# wii.net
KiCad netlist of a schematic drawn in EAGLE
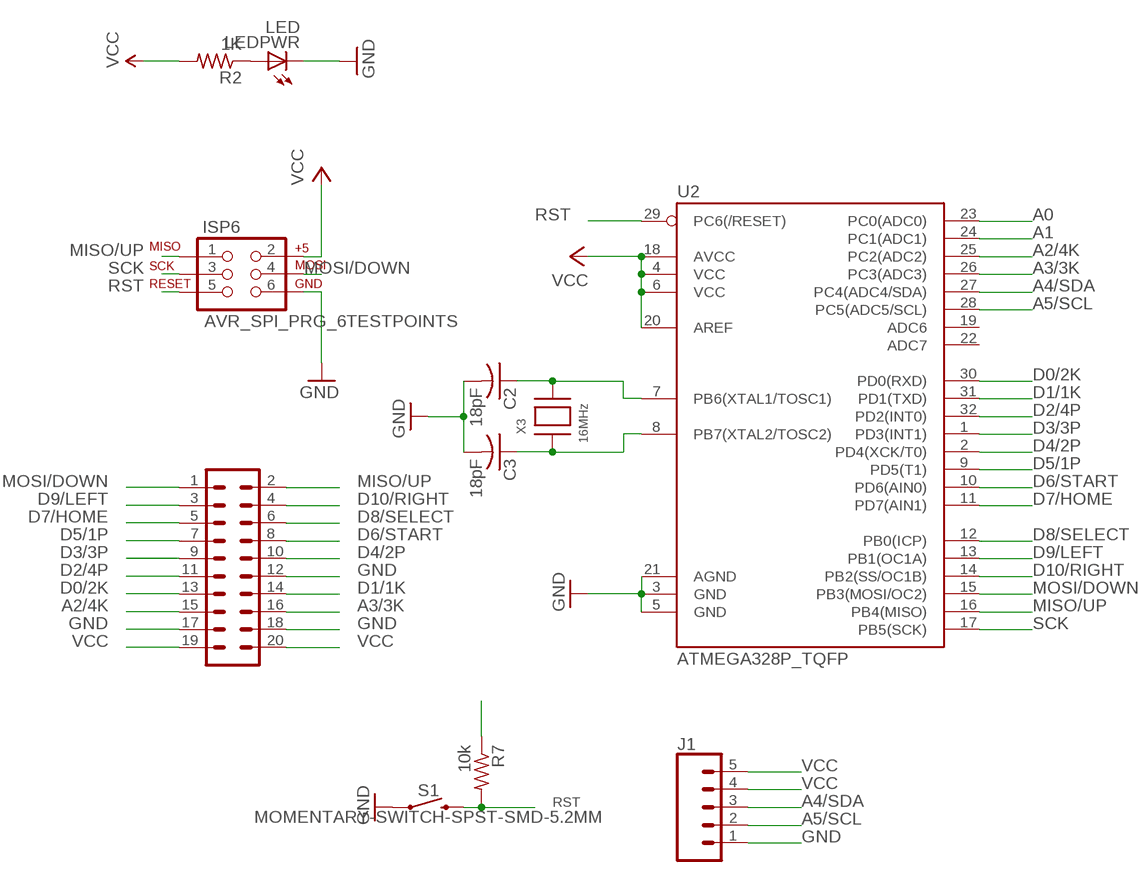
[diagram p0: schematic, sheet 1]

(export (version "E")
  (design (tool "Eeschema 10.0.6"))
  (components
    (comp (ref "C2")
      (value "18pF")
      (footprint "eagle-import:C0805")
      (libsource (lib "eagle-import") (part "C-USC0805"))
    )
    (comp (ref "C3")
      (value "18pF")
      (footprint "eagle-import:C0805")
      (libsource (lib "eagle-import") (part "C-USC0805"))
    )
    (comp (ref "ISP6")
      (value "AVR_SPI_PRG_6TESTPOINTS")
      (footprint "eagle-import:2X3_TEST_POINTS")
      (libsource (lib "eagle-import") (part "AVR_SPI_PRG_6TESTPOINTS"))
    )
    (comp (ref "J1")
      (value "CONN_05")
      (footprint "eagle-import:1X05")
      (libsource (lib "eagle-import") (part "CONN_05"))
    )
    (comp (ref "LEDPWR")
      (value "LED")
      (footprint "eagle-import:CHIPLED_0805")
      (libsource (lib "eagle-import") (part "LEDCHIPLED_0805"))
    )
    (comp (ref "R2")
      (value "1K")
      (footprint "eagle-import:R0805")
      (libsource (lib "eagle-import") (part "R-US_R0805"))
    )
    (comp (ref "R7")
      (value "10k")
      (footprint "eagle-import:R0805")
      (libsource (lib "eagle-import") (part "R-US_R0805"))
    )
    (comp (ref "S1")
      (value "MOMENTARY-SWITCH-SPST-SMD-5.2MM")
      (footprint "eagle-import:TACTILE_SWITCH_SMD_5.2MM")
      (libsource (lib "eagle-import") (part "MOMENTARY-SWITCH-SPST-SMD-5.2MM"))
    )
    (comp (ref "U$1")
      (value "20 pin breakout")
      (footprint "eagle-import:2X10_ROUND_NOSILK")
      (libsource (lib "eagle-import") (part "M10X2ROUND_NOSILK"))
    )
    (comp (ref "U2")
      (value "ATMEGA328P_TQFP")
      (footprint "eagle-import:TQFP32-08")
      (libsource (lib "eagle-import") (part "ATMEGA328P_TQFP"))
    )
    (comp (ref "X3")
      (value "16MHz")
      (footprint "eagle-import:NX5032")
      (libsource (lib "eagle-import") (part "XTALNX5032"))
    )
  )
  (nets
    (net (code "1") (name "/A0") (class "Default")
      (node (ref "U2") (pin "23") (pinfunction "PC0(ADC0)_23") (pintype "bidirectional"))
    )
    (net (code "2") (name "/A1") (class "Default")
      (node (ref "U2") (pin "24") (pinfunction "PC1(ADC1)_24") (pintype "bidirectional"))
    )
    (net (code "3") (name "/A2{slash}4K") (class "Default")
      (node (ref "U$1") (pin "15") (pinfunction "15_15") (pintype "passive"))
      (node (ref "U2") (pin "25") (pinfunction "PC2(ADC2)_25") (pintype "bidirectional"))
    )
    (net (code "4") (name "/A3{slash}3K") (class "Default")
      (node (ref "U$1") (pin "16") (pinfunction "16_16") (pintype "passive"))
      (node (ref "U2") (pin "26") (pinfunction "PC3(ADC3)_26") (pintype "bidirectional"))
    )
    (net (code "5") (name "/A4{slash}SDA") (class "Default")
      (node (ref "J1") (pin "3") (pinfunction "3_3") (pintype "passive"))
      (node (ref "U2") (pin "27") (pinfunction "PC4(ADC4/SDA)_27") (pintype "bidirectional"))
    )
    (net (code "6") (name "/A5{slash}SCL") (class "Default")
      (node (ref "J1") (pin "2") (pinfunction "2_2") (pintype "passive"))
      (node (ref "U2") (pin "28") (pinfunction "PC5(ADC5/SCL)_28") (pintype "bidirectional"))
    )
    (net (code "7") (name "/D0{slash}2K") (class "Default")
      (node (ref "U$1") (pin "13") (pinfunction "13_13") (pintype "passive"))
      (node (ref "U2") (pin "30") (pinfunction "PD0(RXD)_30") (pintype "bidirectional"))
    )
    (net (code "8") (name "/D1{slash}1K") (class "Default")
      (node (ref "U$1") (pin "14") (pinfunction "14_14") (pintype "passive"))
      (node (ref "U2") (pin "31") (pinfunction "PD1(TXD)_31") (pintype "bidirectional"))
    )
    (net (code "9") (name "/D2{slash}4P") (class "Default")
      (node (ref "U$1") (pin "11") (pinfunction "11_11") (pintype "passive"))
      (node (ref "U2") (pin "32") (pinfunction "PD2(INT0)_32") (pintype "bidirectional"))
    )
    (net (code "10") (name "/D3{slash}3P") (class "Default")
      (node (ref "U$1") (pin "9") (pinfunction "9_9") (pintype "passive"))
      (node (ref "U2") (pin "1") (pinfunction "PD3(INT1)_1") (pintype "bidirectional"))
    )
    (net (code "11") (name "/D4{slash}2P") (class "Default")
      (node (ref "U$1") (pin "10") (pinfunction "10_10") (pintype "passive"))
      (node (ref "U2") (pin "2") (pinfunction "PD4(XCK/T0)_2") (pintype "bidirectional"))
    )
    (net (code "12") (name "/D5{slash}1P") (class "Default")
      (node (ref "U$1") (pin "7") (pinfunction "7_7") (pintype "passive"))
      (node (ref "U2") (pin "9") (pinfunction "PD5(T1)_9") (pintype "bidirectional"))
    )
    (net (code "13") (name "/D6{slash}START") (class "Default")
      (node (ref "U$1") (pin "8") (pinfunction "8_8") (pintype "passive"))
      (node (ref "U2") (pin "10") (pinfunction "PD6(AIN0)_10") (pintype "bidirectional"))
    )
    (net (code "14") (name "/D7{slash}HOME") (class "Default")
      (node (ref "U$1") (pin "5") (pinfunction "5_5") (pintype "passive"))
      (node (ref "U2") (pin "11") (pinfunction "PD7(AIN1)_11") (pintype "bidirectional"))
    )
    (net (code "15") (name "/D8{slash}SELECT") (class "Default")
      (node (ref "U$1") (pin "6") (pinfunction "6_6") (pintype "passive"))
      (node (ref "U2") (pin "12") (pinfunction "PB0(ICP)_12") (pintype "bidirectional"))
    )
    (net (code "16") (name "/D9{slash}LEFT") (class "Default")
      (node (ref "U$1") (pin "3") (pinfunction "3_3") (pintype "passive"))
      (node (ref "U2") (pin "13") (pinfunction "PB1(OC1A)_13") (pintype "bidirectional"))
    )
    (net (code "17") (name "/D10{slash}RIGHT") (class "Default")
      (node (ref "U$1") (pin "4") (pinfunction "4_4") (pintype "passive"))
      (node (ref "U2") (pin "14") (pinfunction "PB2(SS/OC1B)_14") (pintype "bidirectional"))
    )
    (net (code "18") (name "/MISO{slash}UP") (class "Default")
      (node (ref "ISP6") (pin "1") (pinfunction "1_1") (pintype "passive"))
      (node (ref "U$1") (pin "2") (pinfunction "2_2") (pintype "passive"))
      (node (ref "U2") (pin "16") (pinfunction "PB4(MISO)_16") (pintype "bidirectional"))
    )
    (net (code "19") (name "/MOSI{slash}DOWN") (class "Default")
      (node (ref "ISP6") (pin "4") (pinfunction "4_4") (pintype "passive"))
      (node (ref "U$1") (pin "1") (pinfunction "1_1") (pintype "passive"))
      (node (ref "U2") (pin "15") (pinfunction "PB3(MOSI/OC2)_15") (pintype "bidirectional"))
    )
    (net (code "20") (name "/RST") (class "Default")
      (node (ref "ISP6") (pin "5") (pinfunction "5_5") (pintype "passive"))
      (node (ref "R7") (pin "2") (pinfunction "2_2") (pintype "passive"))
      (node (ref "S1") (pin "3") (pinfunction "2_3") (pintype "passive"))
      (node (ref "U2") (pin "29") (pinfunction "PC6(/RESET)_29") (pintype "bidirectional"))
    )
    (net (code "21") (name "/SCK") (class "Default")
      (node (ref "ISP6") (pin "3") (pinfunction "3_3") (pintype "passive"))
      (node (ref "U2") (pin "17") (pinfunction "PB5(SCK)_17") (pintype "bidirectional"))
    )
    (net (code "22") (name "GND") (class "Default")
      (node (ref "C2") (pin "2") (pinfunction "2_2") (pintype "passive"))
      (node (ref "C3") (pin "2") (pinfunction "2_2") (pintype "passive"))
      (node (ref "ISP6") (pin "6") (pinfunction "6_6") (pintype "passive"))
      (node (ref "J1") (pin "1") (pinfunction "1_1") (pintype "passive"))
      (node (ref "LEDPWR") (pin "C") (pinfunction "C_C") (pintype "passive"))
      (node (ref "S1") (pin "1") (pinfunction "1_1") (pintype "passive"))
      (node (ref "U$1") (pin "12") (pinfunction "12_12") (pintype "passive"))
      (node (ref "U$1") (pin "17") (pinfunction "17_17") (pintype "passive"))
      (node (ref "U$1") (pin "18") (pinfunction "18_18") (pintype "passive"))
      (node (ref "U2") (pin "21") (pinfunction "AGND_21") (pintype "bidirectional"))
      (node (ref "U2") (pin "3") (pinfunction "GND_3") (pintype "bidirectional"))
      (node (ref "U2") (pin "5") (pinfunction "GND_5") (pintype "bidirectional"))
    )
    (net (code "23") (name "Net-(LEDPWR-PadA)") (class "Default")
      (node (ref "LEDPWR") (pin "A") (pinfunction "A_A") (pintype "passive"))
      (node (ref "R2") (pin "1") (pinfunction "1_1") (pintype "passive"))
    )
    (net (code "24") (name "Net-(U2-PB6(XTAL1{slash}TOSC1))") (class "Default")
      (node (ref "C2") (pin "1") (pinfunction "1_1") (pintype "passive"))
      (node (ref "U2") (pin "7") (pinfunction "PB6(XTAL1/TOSC1)_7") (pintype "bidirectional"))
      (node (ref "X3") (pin "P$2") (pinfunction "P$2_P$2") (pintype "bidirectional"))
    )
    (net (code "25") (name "Net-(U2-PB7(XTAL2{slash}TOSC2))") (class "Default")
      (node (ref "C3") (pin "1") (pinfunction "1_1") (pintype "passive"))
      (node (ref "U2") (pin "8") (pinfunction "PB7(XTAL2/TOSC2)_8") (pintype "bidirectional"))
      (node (ref "X3") (pin "P$1") (pinfunction "P$1_P$1") (pintype "bidirectional"))
    )
    (net (code "26") (name "VCC") (class "Default")
      (node (ref "ISP6") (pin "2") (pinfunction "2_2") (pintype "passive"))
      (node (ref "J1") (pin "4") (pinfunction "4_4") (pintype "passive"))
      (node (ref "J1") (pin "5") (pinfunction "5_5") (pintype "passive"))
      (node (ref "R2") (pin "2") (pinfunction "2_2") (pintype "passive"))
      (node (ref "R7") (pin "1") (pinfunction "1_1") (pintype "passive"))
      (node (ref "U$1") (pin "19") (pinfunction "19_19") (pintype "passive"))
      (node (ref "U$1") (pin "20") (pinfunction "20_20") (pintype "passive"))
      (node (ref "U2") (pin "18") (pinfunction "AVCC_18") (pintype "bidirectional"))
      (node (ref "U2") (pin "20") (pinfunction "AREF_20") (pintype "bidirectional"))
      (node (ref "U2") (pin "4") (pinfunction "VCC_4") (pintype "bidirectional"))
      (node (ref "U2") (pin "6") (pinfunction "VCC_6") (pintype "bidirectional"))
    )
    (net (code "27") (name "unconnected-(U2-ADC6-Pad19)") (class "Default")
      (node (ref "U2") (pin "19") (pinfunction "ADC6_19") (pintype "bidirectional"))
    )
    (net (code "28") (name "unconnected-(U2-ADC7-Pad22)") (class "Default")
      (node (ref "U2") (pin "22") (pinfunction "ADC7_22") (pintype "bidirectional"))
    )
  )
)
